# bjtceamp.net
KiCad netlist of a schematic drawn in Altium Designer
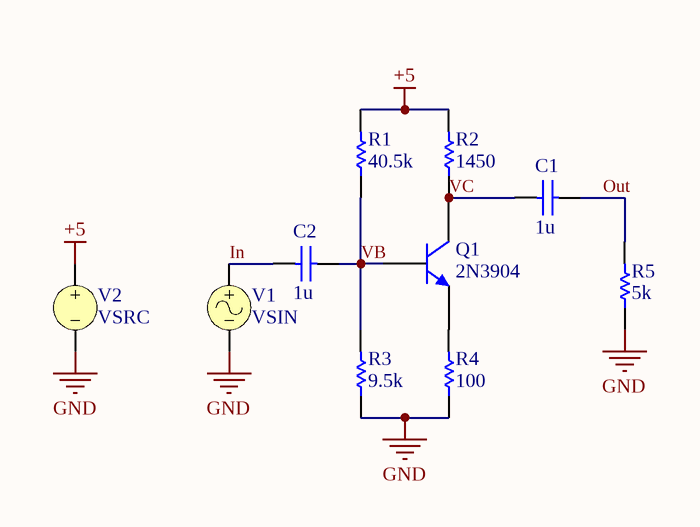
[diagram p0: bjtceamp.SchDoc]

(export (version "E")
  (design (tool "Eeschema 10.0.6"))
  (components
    (comp (ref "C1")
      (value "1u")
      (footprint "RAD-0.3")
      (description "Capacitor")
      (fields (field (name "PUBLISHER") "Altium Limited"))
      (libsource (lib "Miscellaneous Devices") (part "Cap"))
    )
    (comp (ref "C2")
      (value "1u")
      (footprint "RAD-0.3")
      (description "Capacitor")
      (fields (field (name "PUBLISHER") "Altium Limited"))
      (libsource (lib "Miscellaneous Devices") (part "Cap"))
    )
    (comp (ref "Q1")
      (value "2N3904")
      (footprint "TO-92A")
      (description "NPN General Purpose Amplifier")
      (fields (field (name "PUBLISHER") "Altium Limited"))
      (libsource (lib "Miscellaneous Devices") (part "2N3904"))
    )
    (comp (ref "R1")
      (value "40.5k")
      (footprint "AXIAL-0.3")
      (description "Resistor")
      (fields (field (name "PUBLISHER") "Altium Limited"))
      (libsource (lib "Miscellaneous Devices") (part "Res1"))
    )
    (comp (ref "R2")
      (value "1450")
      (footprint "AXIAL-0.3")
      (description "Resistor")
      (fields (field (name "PUBLISHER") "Altium Limited"))
      (libsource (lib "Miscellaneous Devices") (part "Res1"))
    )
    (comp (ref "R3")
      (value "9.5k")
      (footprint "AXIAL-0.3")
      (description "Resistor")
      (fields (field (name "PUBLISHER") "Altium Limited"))
      (libsource (lib "Miscellaneous Devices") (part "Res1"))
    )
    (comp (ref "R4")
      (value "100")
      (footprint "AXIAL-0.3")
      (description "Resistor")
      (fields (field (name "PUBLISHER") "Altium Limited"))
      (libsource (lib "Miscellaneous Devices") (part "Res1"))
    )
    (comp (ref "R5")
      (value "5k")
      (footprint "AXIAL-0.3")
      (description "Resistor")
      (fields (field (name "PUBLISHER") "Altium Limited"))
      (libsource (lib "Miscellaneous Devices") (part "Res1"))
    )
    (comp (ref "V1")
      (value "VSIN")
      (description "Sinusoidal Voltage Source")
      (fields (field (name "PUBLISHER") "Altium Limited"))
      (libsource (lib "Simulation Sources") (part "VSIN"))
    )
    (comp (ref "V2")
      (value "VSRC")
      (description "Voltage Source")
      (fields (field (name "PUBLISHER") "Altium Limited"))
      (libsource (lib "Simulation Sources") (part "VSRC"))
    )
  )
  (nets
    (net (code "1") (name "+5") (class "Default")
      (node (ref "R1") (pin "2") (pinfunction "2_2") (pintype "passive"))
      (node (ref "R2") (pin "2") (pinfunction "2_2") (pintype "passive"))
      (node (ref "V2") (pin "1") (pinfunction "1_1") (pintype "passive"))
    )
    (net (code "2") (name "/In") (class "Default")
      (node (ref "C2") (pin "2") (pinfunction "2_2") (pintype "passive"))
      (node (ref "V1") (pin "1") (pinfunction "1_1") (pintype "passive"))
    )
    (net (code "3") (name "/Out") (class "Default")
      (node (ref "C1") (pin "1") (pinfunction "1_1") (pintype "passive"))
      (node (ref "R5") (pin "2") (pinfunction "2_2") (pintype "passive"))
    )
    (net (code "4") (name "/VB") (class "Default")
      (node (ref "C2") (pin "1") (pinfunction "1_1") (pintype "passive"))
      (node (ref "Q1") (pin "2") (pinfunction "B_2") (pintype "passive"))
      (node (ref "R1") (pin "1") (pinfunction "1_1") (pintype "passive"))
      (node (ref "R3") (pin "2") (pinfunction "2_2") (pintype "passive"))
    )
    (net (code "5") (name "/VC") (class "Default")
      (node (ref "C1") (pin "2") (pinfunction "2_2") (pintype "passive"))
      (node (ref "Q1") (pin "3") (pinfunction "C_3") (pintype "passive"))
      (node (ref "R2") (pin "1") (pinfunction "1_1") (pintype "passive"))
    )
    (net (code "6") (name "GND") (class "Default")
      (node (ref "R3") (pin "1") (pinfunction "1_1") (pintype "passive"))
      (node (ref "R4") (pin "1") (pinfunction "1_1") (pintype "passive"))
      (node (ref "R5") (pin "1") (pinfunction "1_1") (pintype "passive"))
      (node (ref "V1") (pin "2") (pinfunction "2_2") (pintype "passive"))
      (node (ref "V2") (pin "2") (pinfunction "2_2") (pintype "passive"))
    )
    (net (code "7") (name "Net-(Q1-E)") (class "Default")
      (node (ref "Q1") (pin "1") (pinfunction "E_1") (pintype "passive"))
      (node (ref "R4") (pin "2") (pinfunction "2_2") (pintype "passive"))
    )
  )
)
